# Motor_Drive_Input.net
KiCad netlist of a schematic drawn in Altium Designer
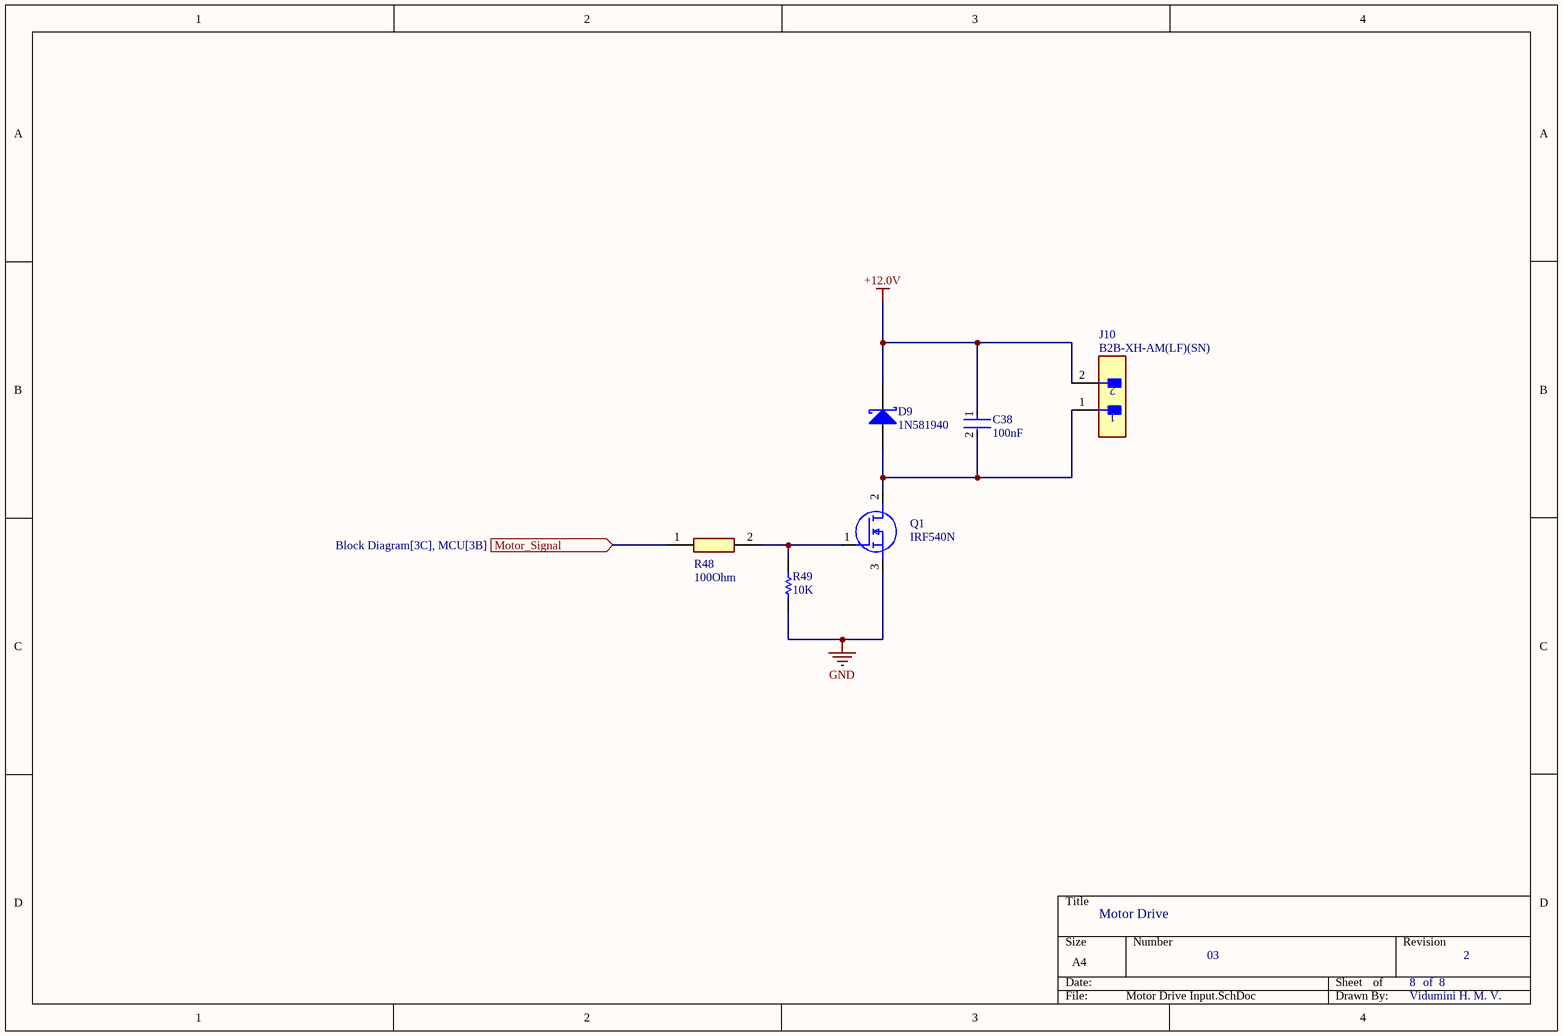
[diagram p0: Motor Drive Input.SchDoc]

(export (version "E")
  (design (tool "Eeschema 10.0.6"))
  (components
    (comp (ref "C38")
      (value "100nF")
      (footprint "FP-1206-L_3_2_0_2-W_1_6_0-IPC_C")
      (description "General Purpose Ceramic Capacitor, 1206, 100nF, 5%, X7R, 15%, 100V")
      (fields (field (name "TOLERANCE") "5%") (field (name "VOLTAGE") "100V"))
      (libsource (lib "Altium Content Vault") (part "b4654b650e69147ec39a6b967a45e02"))
    )
    (comp (ref "D9")
      (value "1N581940")
      (footprint "DIOD-DO-41-P-2")
      (description "Schottky Barrier Rectifier, 1 A, 20 V, -65 to 125 degC, 2-Pin DO-41, RoHS, Tape and Reel")
      (fields (field (name "MANUFACTURER") "DiodesIncorporated"))
      (libsource (lib "Altium Content Vault") (part "DSKY-AK-2"))
    )
    (comp (ref "J10")
      (value "B2B-XH-AM(LF)(SN)")
      (footprint "FP-B2B-XH-AM_LF_SN-MFG")
      (description "CONN HEADER VERT 2POS 2.5MM")
      (libsource (lib "Altium Content Vault") (part "3bc925449376181038e59eaffc5286c"))
    )
    (comp (ref "Q1")
      (value "IRF540N")
      (footprint "SamacSys:TO254P469X1042X1967-3P")
      (description "MOSFET (N-Channel)")
      (libsource (lib "*") (part "IRF540N"))
    )
    (comp (ref "R48")
      (value "100Ohm")
      (footprint "SamacSys:RESC2013X65N")
      (description "Resistor")
      (fields (field (name "MANUFACTURER_PART_NUMBER") "0805W8F1000T5E"))
      (libsource (lib "*") (part "0805W8F1000T5E"))
    )
    (comp (ref "R49")
      (value "10K")
      (footprint "RESC3116X65X40ML10T20")
      (description "Chip Resistor, 10 KOhm, +/- 1%, 0.25 W, -55 to 155 degC, 1206 (3216 Metric), RoHS, Tape and Reel")
      (fields (field (name "TOLERANCE") "1%") (field (name "MANUFACTURER") "Yageo"))
      (libsource (lib "Altium Content Vault") (part "RES-2"))
    )
  )
  (nets
    (net (code "1") (name "+12.0V") (class "Default")
      (node (ref "C38") (pin "1") (pinfunction "1_1") (pintype "passive"))
      (node (ref "D9") (pin "2") (pinfunction "K_2") (pintype "passive"))
      (node (ref "J10") (pin "2") (pinfunction "2_2") (pintype "passive"))
    )
    (net (code "2") (name "/Motor_Signal") (class "Default")
      (node (ref "R48") (pin "1") (pinfunction "1_1") (pintype "passive"))
    )
    (net (code "3") (name "GND") (class "Default")
      (node (ref "Q1") (pin "3") (pinfunction "S_3") (pintype "passive"))
      (node (ref "R49") (pin "1") (pinfunction "1_1") (pintype "passive"))
    )
    (net (code "4") (name "Net-(D9-A)") (class "Default")
      (node (ref "C38") (pin "2") (pinfunction "2_2") (pintype "passive"))
      (node (ref "D9") (pin "1") (pinfunction "A_1") (pintype "passive"))
      (node (ref "J10") (pin "1") (pinfunction "1_1") (pintype "passive"))
      (node (ref "Q1") (pin "2") (pinfunction "D_2") (pintype "passive"))
    )
    (net (code "5") (name "Net-(Q1-G)") (class "Default")
      (node (ref "Q1") (pin "1") (pinfunction "G_1") (pintype "passive"))
      (node (ref "R48") (pin "2") (pinfunction "2_2") (pintype "passive"))
      (node (ref "R49") (pin "2") (pinfunction "2_2") (pintype "passive"))
    )
  )
)
